# Communications_Power.net
KiCad netlist of a schematic drawn in Altium Designer
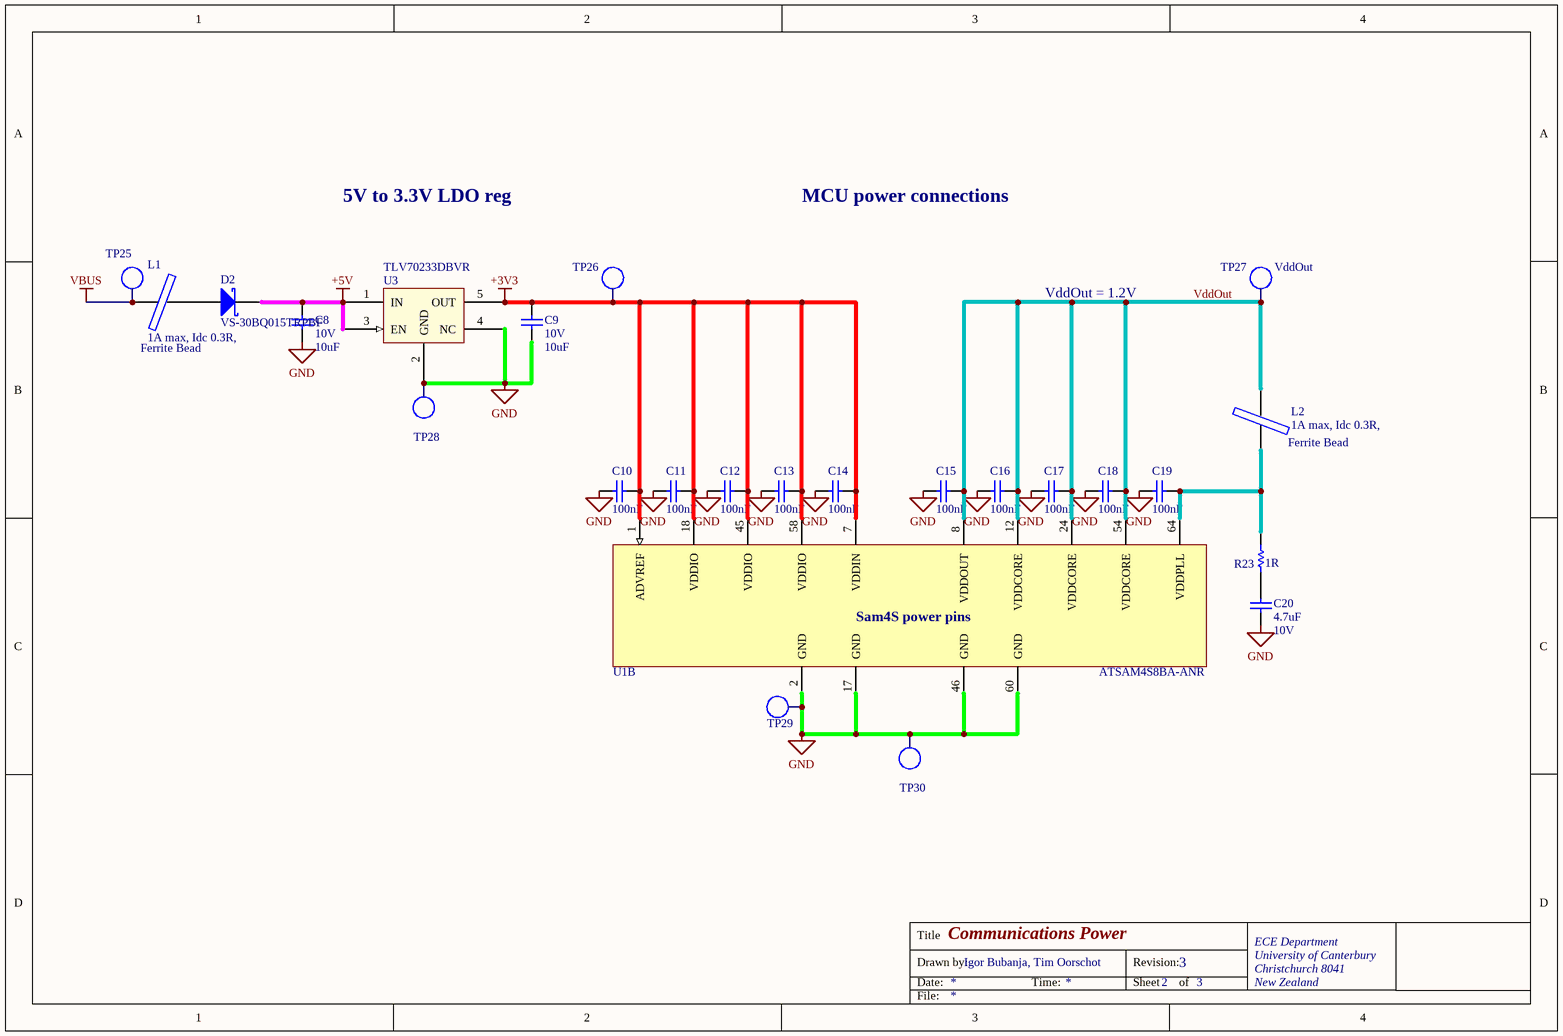
[diagram p0: Communications_Power.SchDoc]

(export (version "E")
  (design (tool "Eeschema 10.0.6"))
  (components
    (comp (ref "C8")
      (value "10uF")
      (footprint "CAPC1608L")
      (description "CAP CER 10UF X5R +-20% 10V 0603")
      (fields (field (name "VOLTAGE - RATED") "10V"))
      (libsource (lib "ECE Components_15_7") (part "CC_10uF_0603"))
    )
    (comp (ref "C9")
      (value "10uF")
      (footprint "CAPC1608L")
      (description "CAP CER 10UF X5R +-20% 10V 0603")
      (fields (field (name "VOLTAGE - RATED") "10V"))
      (libsource (lib "ECE Components_15_7") (part "CC_10uF_0603"))
    )
    (comp (ref "C10")
      (value "100nF")
      (footprint "CAPC1608L")
      (description "CAP CER 100nF X7R +-10% 50V 0603")
      (libsource (lib "ECE Components_15_7") (part "CC_100nF_0603"))
    )
    (comp (ref "C11")
      (value "100nF")
      (footprint "CAPC1608L")
      (description "CAP CER 100nF X7R +-10% 50V 0603")
      (libsource (lib "ECE Components_15_7") (part "CC_100nF_0603"))
    )
    (comp (ref "C12")
      (value "100nF")
      (footprint "CAPC1608L")
      (description "CAP CER 100nF X7R +-10% 50V 0603")
      (libsource (lib "ECE Components_15_7") (part "CC_100nF_0603"))
    )
    (comp (ref "C13")
      (value "100nF")
      (footprint "CAPC1608L")
      (description "CAP CER 100nF X7R +-10% 50V 0603")
      (libsource (lib "ECE Components_15_7") (part "CC_100nF_0603"))
    )
    (comp (ref "C14")
      (value "100nF")
      (footprint "CAPC1608L")
      (description "CAP CER 100nF X7R +-10% 50V 0603")
      (libsource (lib "ECE Components_15_7") (part "CC_100nF_0603"))
    )
    (comp (ref "C15")
      (value "100nF")
      (footprint "CAPC1608L")
      (description "CAP CER 100nF X7R +-10% 50V 0603")
      (libsource (lib "ECE Components_15_7") (part "CC_100nF_0603"))
    )
    (comp (ref "C16")
      (value "100nF")
      (footprint "CAPC1608L")
      (description "CAP CER 100nF X7R +-10% 50V 0603")
      (libsource (lib "ECE Components_15_7") (part "CC_100nF_0603"))
    )
    (comp (ref "C17")
      (value "100nF")
      (footprint "CAPC1608L")
      (description "CAP CER 100nF X7R +-10% 50V 0603")
      (libsource (lib "ECE Components_15_7") (part "CC_100nF_0603"))
    )
    (comp (ref "C18")
      (value "100nF")
      (footprint "CAPC1608L")
      (description "CAP CER 100nF X7R +-10% 50V 0603")
      (libsource (lib "ECE Components_15_7") (part "CC_100nF_0603"))
    )
    (comp (ref "C19")
      (value "100nF")
      (footprint "CAPC1608L")
      (description "CAP CER 100nF X7R +-10% 50V 0603")
      (libsource (lib "ECE Components_15_7") (part "CC_100nF_0603"))
    )
    (comp (ref "C20")
      (value "4.7uF")
      (footprint "CAPC1608N")
      (description "CAP CER 4.7uF X5R +-20%  10V 0603")
      (fields (field (name "MAX VOLTAGE") "10V"))
      (libsource (lib "ECE Components_15_7") (part "CC_4.7uF_0603"))
    )
    (comp (ref "D2")
      (value "VS-30BQ015TRPBF")
      (footprint "SMC")
      (description "DIODE SCHOTTKY 15V 3A SMC")
      (fields
        (field (name "MANUFACTURER") "Vishay Semiconductor Diodes Division")
        (field (name "MANUFACTURER PART NUMBER") "VS-30BQ015TRPBF")
      )
      (libsource (lib "ECE Components_15_8") (part "DS_VS-30BQD015TRPBF"))
    )
    (comp (ref "L1")
      (value "Ferrite Bead")
      (footprint "INDC3216L")
      (description "Ferrite Bead, Rdc 0.3R, Z100MHZ 600R, Imax 1A, SMD 1206")
      (fields
        (field (name "MANUFACTURER") "FAIR-RITE")
        (field (name "MANUFACTURER PART NUMBER") "2512066017Y1")
        (field (name "ALTIUM_VALUE") "1A max, Idc 0.3R,")
      )
      (libsource (lib "ECE Components_15_7") (part "IN_Ferrite-Bead"))
    )
    (comp (ref "L2")
      (value "Ferrite Bead")
      (footprint "INDC3216L")
      (description "Ferrite Bead, Rdc 0.3R, Z100MHZ 600R, Imax 1A, SMD 1206")
      (fields
        (field (name "MANUFACTURER") "FAIR-RITE")
        (field (name "MANUFACTURER PART NUMBER") "2512066017Y1")
        (field (name "ALTIUM_VALUE") "1A max, Idc 0.3R,")
      )
      (libsource (lib "ECE Components_15_7") (part "IN_Ferrite-Bead"))
    )
    (comp (ref "R23")
      (value "1R")
      (footprint "RESC3216L")
      (description "RES 1R OHM 1/4W 5% 1206 SMD")
      (libsource (lib "ECE Components_15_7") (part "RT_1R"))
    )
    (comp (ref "TP25")
      (value "V_Bus")
      (footprint "TP_0805")
      (description "Test Point 2.0X0.9X1.2mm SMD")
      (fields
        (field (name "MANUFACTURER") "TE Connectivity AMP Connectors")
        (field (name "MANUFACTURER PART NUMBER") "1625854-2")
      )
      (libsource (lib "ECE Components_15_7") (part "TP_0805"))
    )
    (comp (ref "TP26")
      (value "3V3")
      (footprint "TP_0805")
      (description "Test Point 2.0X0.9X1.2mm SMD")
      (fields
        (field (name "MANUFACTURER") "TE Connectivity AMP Connectors")
        (field (name "MANUFACTURER PART NUMBER") "1625854-2")
      )
      (libsource (lib "ECE Components_15_7") (part "TP_0805"))
    )
    (comp (ref "TP27")
      (value "VddOut")
      (footprint "TP_0805")
      (description "Test Point 2.0X0.9X1.2mm SMD")
      (fields
        (field (name "MANUFACTURER") "TE Connectivity AMP Connectors")
        (field (name "MANUFACTURER PART NUMBER") "1625854-2")
      )
      (libsource (lib "ECE Components_15_7") (part "TP_0805"))
    )
    (comp (ref "TP28")
      (value "Gnd")
      (footprint "TP_0805")
      (description "Test Point 2.0X0.9X1.2mm SMD")
      (fields
        (field (name "MANUFACTURER") "TE Connectivity AMP Connectors")
        (field (name "MANUFACTURER PART NUMBER") "1625854-2")
      )
      (libsource (lib "ECE Components_15_7") (part "TP_0805"))
    )
    (comp (ref "TP29")
      (value "Gnd")
      (footprint "TP_0805")
      (description "Test Point 2.0X0.9X1.2mm SMD")
      (fields
        (field (name "MANUFACTURER") "TE Connectivity AMP Connectors")
        (field (name "MANUFACTURER PART NUMBER") "1625854-2")
      )
      (libsource (lib "ECE Components_15_7") (part "TP_0805"))
    )
    (comp (ref "TP30")
      (value "Gnd")
      (footprint "TP_0805")
      (description "Test Point 2.0X0.9X1.2mm SMD")
      (fields
        (field (name "MANUFACTURER") "TE Connectivity AMP Connectors")
        (field (name "MANUFACTURER PART NUMBER") "1625854-2")
      )
      (libsource (lib "ECE Components_15_7") (part "TP_0805"))
    )
    (comp (ref "U1")
      (value "ATSAM4S8BA-ANR")
      (footprint "LQFP64_L")
      (description "IC MCU 32BIT 512KB FLASH 64LQFP")
      (fields (field (name "MANUFACTURER") "Atmel"))
      (libsource (lib "ECE Components_15_7") (part "SE_ATSAM4S16BA-MU"))
    )
    (comp (ref "U3")
      (value "TLV70233DBVR")
      (footprint "SOT95P280X145-5N")
      (description "IC REG LDO 3.3V 0.3A SOT23-5")
      (fields
        (field (name "MANUFACTURER") "Texas Instruments")
        (field (name "MANUFACTURER PART NUMBER") "TLV70233DBVR")
      )
      (libsource (lib "ECE Components_15_7") (part "SV_TLV70233DBVR"))
    )
  )
  (nets
    (net (code "1") (name "+3V3") (class "Default")
      (node (ref "C10") (pin "2") (pinfunction "2_2") (pintype "passive"))
      (node (ref "C11") (pin "2") (pinfunction "2_2") (pintype "passive"))
      (node (ref "C12") (pin "2") (pinfunction "2_2") (pintype "passive"))
      (node (ref "C13") (pin "2") (pinfunction "2_2") (pintype "passive"))
      (node (ref "C14") (pin "2") (pinfunction "2_2") (pintype "passive"))
      (node (ref "C9") (pin "1") (pinfunction "1_1") (pintype "passive"))
      (node (ref "TP26") (pin "1") (pinfunction "TP_1") (pintype "passive"))
      (node (ref "U1") (pin "1") (pinfunction "ADVREF_1") (pintype "input"))
      (node (ref "U1") (pin "18") (pinfunction "VDDIO_18") (pintype "power_in"))
      (node (ref "U1") (pin "45") (pinfunction "VDDIO_45") (pintype "power_in"))
      (node (ref "U1") (pin "58") (pinfunction "VDDIO_58") (pintype "power_in"))
      (node (ref "U1") (pin "7") (pinfunction "VDDIN_7") (pintype "power_in"))
      (node (ref "U3") (pin "5") (pinfunction "OUT_5") (pintype "power_in"))
    )
    (net (code "2") (name "+5V") (class "Default")
      (node (ref "C8") (pin "1") (pinfunction "1_1") (pintype "passive"))
      (node (ref "D2") (pin "2") (pinfunction "K_2") (pintype "passive"))
      (node (ref "U3") (pin "1") (pinfunction "IN_1") (pintype "power_in"))
      (node (ref "U3") (pin "3") (pinfunction "EN_3") (pintype "input"))
    )
    (net (code "3") (name "/VddOut") (class "Default")
      (node (ref "C15") (pin "2") (pinfunction "2_2") (pintype "passive"))
      (node (ref "C16") (pin "2") (pinfunction "2_2") (pintype "passive"))
      (node (ref "C17") (pin "2") (pinfunction "2_2") (pintype "passive"))
      (node (ref "C18") (pin "2") (pinfunction "2_2") (pintype "passive"))
      (node (ref "L2") (pin "2") (pinfunction "2_2") (pintype "passive"))
      (node (ref "TP27") (pin "1") (pinfunction "TP_1") (pintype "passive"))
      (node (ref "U1") (pin "12") (pinfunction "VDDCORE_12") (pintype "power_in"))
      (node (ref "U1") (pin "24") (pinfunction "VDDCORE_24") (pintype "power_in"))
      (node (ref "U1") (pin "54") (pinfunction "VDDCORE_54") (pintype "power_in"))
      (node (ref "U1") (pin "8") (pinfunction "VDDOUT_8") (pintype "power_in"))
    )
    (net (code "4") (name "GND") (class "Default")
      (node (ref "C10") (pin "1") (pinfunction "1_1") (pintype "passive"))
      (node (ref "C11") (pin "1") (pinfunction "1_1") (pintype "passive"))
      (node (ref "C12") (pin "1") (pinfunction "1_1") (pintype "passive"))
      (node (ref "C13") (pin "1") (pinfunction "1_1") (pintype "passive"))
      (node (ref "C14") (pin "1") (pinfunction "1_1") (pintype "passive"))
      (node (ref "C15") (pin "1") (pinfunction "1_1") (pintype "passive"))
      (node (ref "C16") (pin "1") (pinfunction "1_1") (pintype "passive"))
      (node (ref "C17") (pin "1") (pinfunction "1_1") (pintype "passive"))
      (node (ref "C18") (pin "1") (pinfunction "1_1") (pintype "passive"))
      (node (ref "C19") (pin "1") (pinfunction "1_1") (pintype "passive"))
      (node (ref "C20") (pin "1") (pinfunction "1_1") (pintype "passive"))
      (node (ref "C8") (pin "2") (pinfunction "2_2") (pintype "passive"))
      (node (ref "C9") (pin "2") (pinfunction "2_2") (pintype "passive"))
      (node (ref "TP28") (pin "1") (pinfunction "TP_1") (pintype "passive"))
      (node (ref "TP29") (pin "1") (pinfunction "TP_1") (pintype "passive"))
      (node (ref "TP30") (pin "1") (pinfunction "TP_1") (pintype "passive"))
      (node (ref "U1") (pin "17") (pinfunction "GND_17") (pintype "power_in"))
      (node (ref "U1") (pin "2") (pinfunction "GND_2") (pintype "power_in"))
      (node (ref "U1") (pin "46") (pinfunction "GND_46") (pintype "power_in"))
      (node (ref "U1") (pin "60") (pinfunction "GND_60") (pintype "power_in"))
      (node (ref "U3") (pin "2") (pinfunction "GND_2") (pintype "power_in"))
      (node (ref "U3") (pin "4") (pinfunction "NC_4") (pintype "passive"))
    )
    (net (code "5") (name "Net-(C20-Pad2)") (class "Default")
      (node (ref "C20") (pin "2") (pinfunction "2_2") (pintype "passive"))
      (node (ref "R23") (pin "1") (pinfunction "1_1") (pintype "passive"))
    )
    (net (code "6") (name "Net-(D2-A)") (class "Default")
      (node (ref "D2") (pin "1") (pinfunction "A_1") (pintype "passive"))
      (node (ref "L1") (pin "2") (pinfunction "2_2") (pintype "passive"))
    )
    (net (code "7") (name "Net-(U1B-VDDPLL)") (class "Default")
      (node (ref "C19") (pin "2") (pinfunction "2_2") (pintype "passive"))
      (node (ref "L2") (pin "1") (pinfunction "1_1") (pintype "passive"))
      (node (ref "R23") (pin "2") (pinfunction "2_2") (pintype "passive"))
      (node (ref "U1") (pin "64") (pinfunction "VDDPLL_64") (pintype "power_in"))
    )
    (net (code "8") (name "VBUS") (class "Default")
      (node (ref "L1") (pin "1") (pinfunction "1_1") (pintype "passive"))
      (node (ref "TP25") (pin "1") (pinfunction "TP_1") (pintype "passive"))
    )
  )
)
